# interface.net
KiCad netlist of a schematic drawn in EAGLE
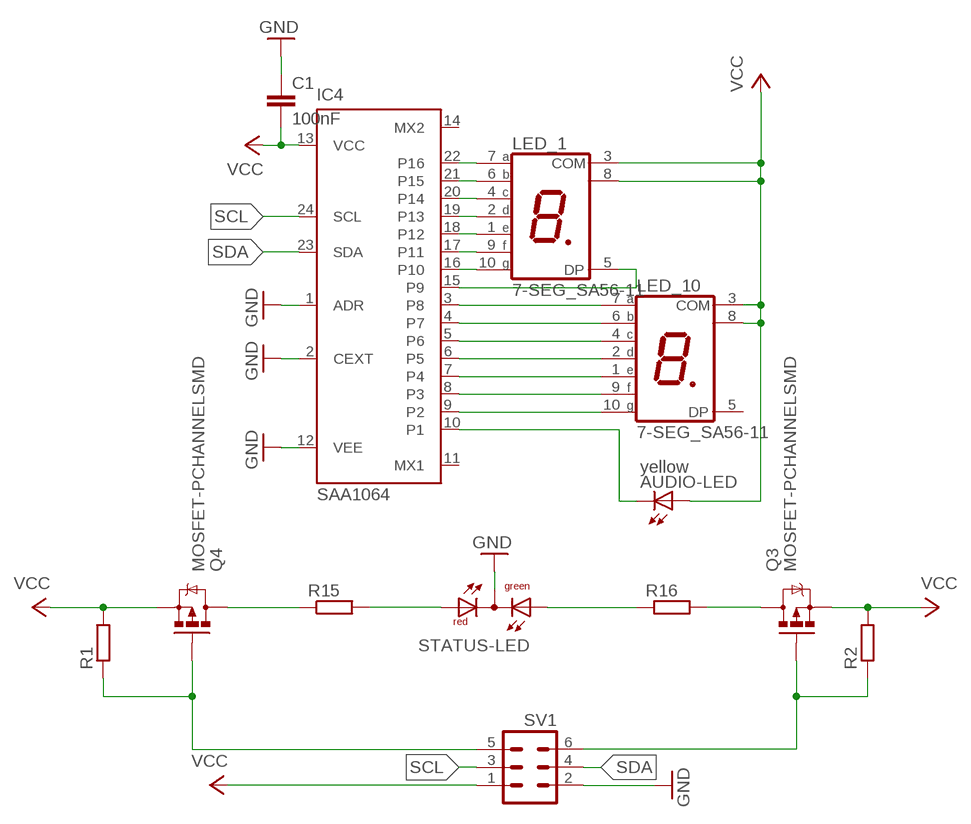
[diagram p0: schematic, sheet 1]
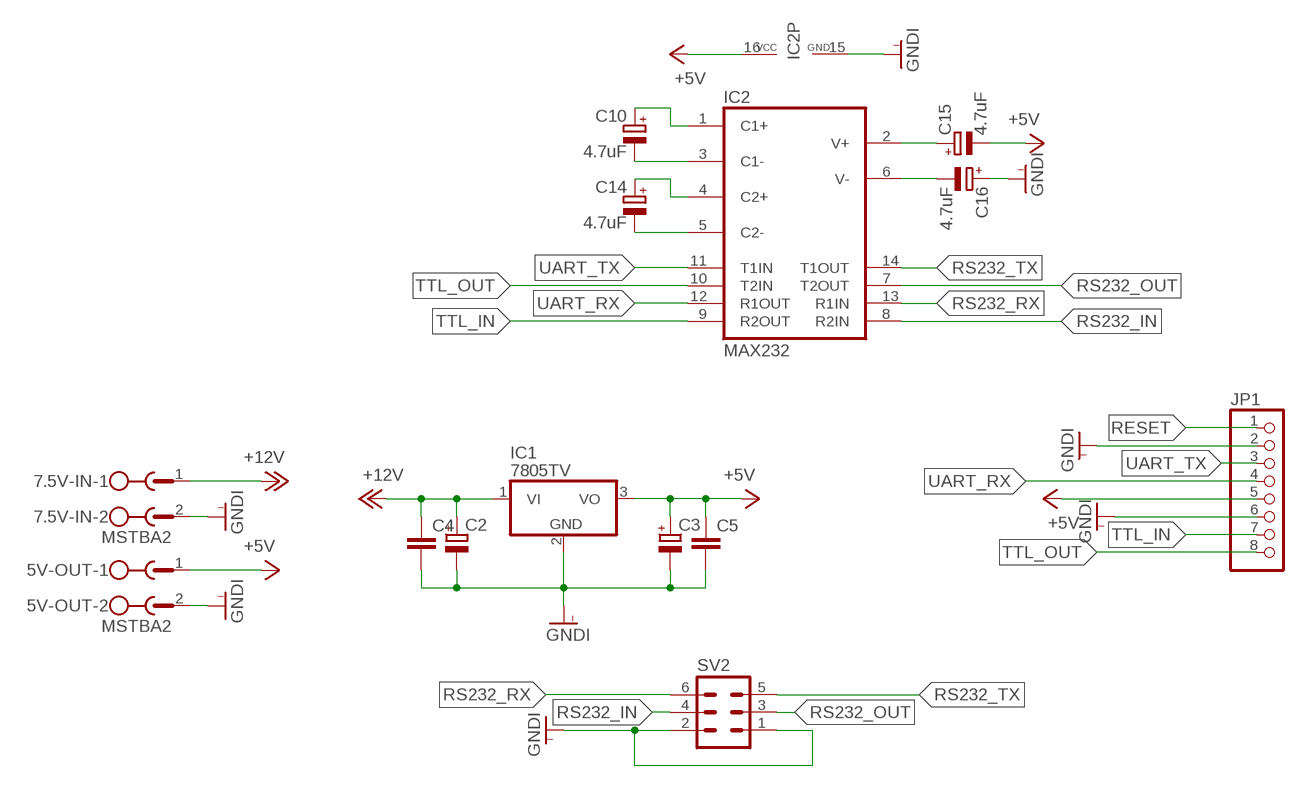
[diagram p1: schematic, sheet 2]
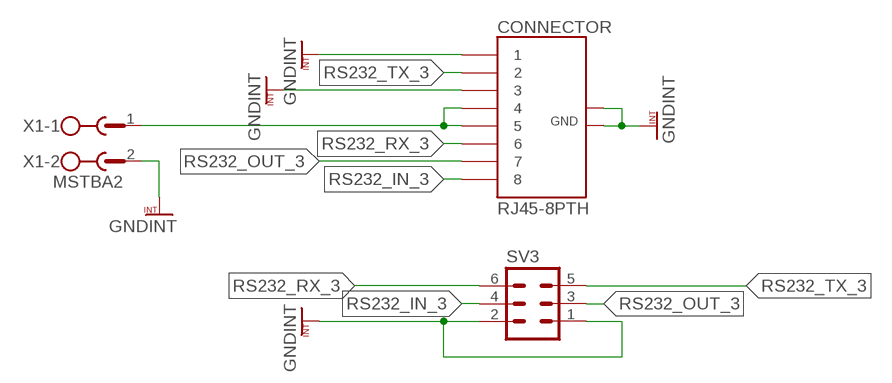
[diagram p2: schematic, sheet 3]

(export (version "E")
  (design (tool "Eeschema 10.0.6"))
  (components
    (comp (ref "CONNECTOR")
      (value "RJ45-8PTH")
      (footprint "eagle-import:RJ45-8")
      (libsource (lib "eagle-import") (part "RJ45-8PTH"))
    )
    (comp (ref "SV3")
      (value "ML6")
      (footprint "eagle-import:ML6")
      (libsource (lib "eagle-import") (part "ML6"))
    )
    (comp (ref "X1")
      (value "MSTBA2")
      (footprint "eagle-import:MSTBA2")
      (fields (field (name "MF") "FARNELL") (field (name "MPN") "1757242"))
      (libsource (lib "eagle-import") (part "MSTBA2"))
    )
    (comp (ref "AUDIO-LED")
      (value "yellow")
      (footprint "eagle-import:LED10MM")
      (libsource (lib "eagle-import") (part "LED10MM"))
    )
    (comp (ref "C1")
      (value "100nF")
      (footprint "eagle-import:C1206")
      (libsource (lib "eagle-import") (part "C-EUC1206"))
    )
    (comp (ref "IC4")
      (value "SAA1064")
      (footprint "eagle-import:DIL24-6")
      (fields (field (name "MPN") "SAA1064/N2,112"))
      (libsource (lib "eagle-import") (part "SAA1064"))
    )
    (comp (ref "LED_1")
      (value "7-SEG_SA56-11")
      (footprint "eagle-import:SA56-11")
      (libsource (lib "eagle-import") (part "7-SEG_SA56-11"))
    )
    (comp (ref "LED_10")
      (value "7-SEG_SA56-11")
      (footprint "eagle-import:SA56-11")
      (libsource (lib "eagle-import") (part "7-SEG_SA56-11"))
    )
    (comp (ref "Q3")
      (value "MOSFET-PCHANNELSMD")
      (footprint "eagle-import:SOT23-3")
      (libsource (lib "eagle-import") (part "MOSFET-PCHANNELSMD"))
    )
    (comp (ref "Q4")
      (value "MOSFET-PCHANNELSMD")
      (footprint "eagle-import:SOT23-3")
      (libsource (lib "eagle-import") (part "MOSFET-PCHANNELSMD"))
    )
    (comp (ref "R1")
      (value "R-EU_R1206")
      (footprint "eagle-import:R1206")
      (libsource (lib "eagle-import") (part "R-EU_R1206"))
    )
    (comp (ref "R2")
      (value "R-EU_R1206")
      (footprint "eagle-import:R1206")
      (libsource (lib "eagle-import") (part "R-EU_R1206"))
    )
    (comp (ref "R15")
      (value "R-EU_R1206")
      (footprint "eagle-import:R1206")
      (libsource (lib "eagle-import") (part "R-EU_R1206"))
    )
    (comp (ref "R16")
      (value "R-EU_R1206")
      (footprint "eagle-import:R1206")
      (libsource (lib "eagle-import") (part "R-EU_R1206"))
    )
    (comp (ref "STATUS-LED")
      (value "DUOLED-RG-C")
      (footprint "eagle-import:DUOLED-C-5MM")
      (libsource (lib "eagle-import") (part "DUOLED-RG-C"))
    )
    (comp (ref "SV1")
      (value "ML6SMD2")
      (footprint "eagle-import:ML6_SMD2")
      (libsource (lib "eagle-import") (part "ML6SMD2"))
    )
    (comp (ref "5V-OUT")
      (value "MSTBA2")
      (footprint "eagle-import:MSTBA2")
      (fields (field (name "MF") "FARNELL") (field (name "MPN") "1757242"))
      (libsource (lib "eagle-import") (part "MSTBA2"))
    )
    (comp (ref "7.5V-IN")
      (value "MSTBA2")
      (footprint "eagle-import:MSTBA2")
      (fields (field (name "MF") "FARNELL") (field (name "MPN") "1757242"))
      (libsource (lib "eagle-import") (part "MSTBA2"))
    )
    (comp (ref "C2")
      (value "CPOL-EUE5-10.5")
      (footprint "eagle-import:E5-10,5")
      (libsource (lib "eagle-import") (part "CPOL-EUE5-10.5"))
    )
    (comp (ref "C3")
      (value "CPOL-EUE5-10.5")
      (footprint "eagle-import:E5-10,5")
      (libsource (lib "eagle-import") (part "CPOL-EUE5-10.5"))
    )
    (comp (ref "C4")
      (value "C-EUC1206")
      (footprint "eagle-import:C1206")
      (libsource (lib "eagle-import") (part "C-EUC1206"))
    )
    (comp (ref "C5")
      (value "C-EUC1206")
      (footprint "eagle-import:C1206")
      (libsource (lib "eagle-import") (part "C-EUC1206"))
    )
    (comp (ref "C10")
      (value "4.7uF")
      (footprint "eagle-import:E2-5")
      (libsource (lib "eagle-import") (part "CPOL-EUE2-5"))
    )
    (comp (ref "C14")
      (value "4.7uF")
      (footprint "eagle-import:E2-5")
      (libsource (lib "eagle-import") (part "CPOL-EUE2-5"))
    )
    (comp (ref "C15")
      (value "4.7uF")
      (footprint "eagle-import:E2-5")
      (libsource (lib "eagle-import") (part "CPOL-EUE2-5"))
    )
    (comp (ref "C16")
      (value "4.7uF")
      (footprint "eagle-import:E2-5")
      (libsource (lib "eagle-import") (part "CPOL-EUE2-5"))
    )
    (comp (ref "IC1")
      (value "7805TV")
      (footprint "eagle-import:TO220V")
      (libsource (lib "eagle-import") (part "78TV05"))
    )
    (comp (ref "IC2")
      (value "MAX232")
      (footprint "eagle-import:DIL16")
      (fields (field (name "MF") "MAXIM") (field (name "MPN") "MAX232ACPE+"))
      (libsource (lib "eagle-import") (part "MAX232"))
    )
    (comp (ref "JP1")
      (value "PINHD-1X8/90")
      (footprint "eagle-import:1X08_90")
      (libsource (lib "eagle-import") (part "PINHD-1X8/90"))
    )
    (comp (ref "SV2")
      (value "ML6")
      (footprint "eagle-import:ML6")
      (libsource (lib "eagle-import") (part "ML6"))
    )
  )
  (nets
    (net (code "1") (name "+5V") (class "Default")
      (node (ref "5V-OUT") (pin "1") (pinfunction "1_1") (pintype "passive"))
      (node (ref "C15") (pin "-") (pinfunction "-_-") (pintype "passive"))
      (node (ref "C3") (pin "+") (pinfunction "+_+") (pintype "passive"))
      (node (ref "C5") (pin "1") (pinfunction "1_1") (pintype "passive"))
      (node (ref "IC1") (pin "3") (pinfunction "VO_3") (pintype "passive"))
      (node (ref "IC2") (pin "16") (pinfunction "VCC_16") (pintype "power_in"))
      (node (ref "JP1") (pin "5") (pinfunction "5_5") (pintype "passive"))
    )
    (net (code "2") (name "+12V") (class "Default")
      (node (ref "7.5V-IN") (pin "1") (pinfunction "1_1") (pintype "passive"))
      (node (ref "C2") (pin "+") (pinfunction "+_+") (pintype "passive"))
      (node (ref "C4") (pin "1") (pinfunction "1_1") (pintype "passive"))
      (node (ref "IC1") (pin "1") (pinfunction "VI_1") (pintype "input"))
    )
    (net (code "3") (name "GND") (class "Default")
      (node (ref "C1") (pin "1") (pinfunction "1_1") (pintype "passive"))
      (node (ref "IC4") (pin "1") (pinfunction "ADR_1") (pintype "input"))
      (node (ref "IC4") (pin "12") (pinfunction "VEE_12") (pintype "power_in"))
      (node (ref "IC4") (pin "2") (pinfunction "CEXT_2") (pintype "input"))
      (node (ref "STATUS-LED") (pin "C") (pinfunction "C_C") (pintype "passive"))
      (node (ref "SV1") (pin "2") (pinfunction "2_2") (pintype "passive"))
    )
    (net (code "4") (name "GNDI") (class "Default")
      (node (ref "5V-OUT") (pin "2") (pinfunction "1_2") (pintype "passive"))
      (node (ref "7.5V-IN") (pin "2") (pinfunction "1_2") (pintype "passive"))
      (node (ref "C16") (pin "+") (pinfunction "+_+") (pintype "passive"))
      (node (ref "C2") (pin "-") (pinfunction "-_-") (pintype "passive"))
      (node (ref "C3") (pin "-") (pinfunction "-_-") (pintype "passive"))
      (node (ref "C4") (pin "2") (pinfunction "2_2") (pintype "passive"))
      (node (ref "C5") (pin "2") (pinfunction "2_2") (pintype "passive"))
      (node (ref "IC1") (pin "2") (pinfunction "GND_2") (pintype "passive"))
      (node (ref "IC2") (pin "15") (pinfunction "GND_15") (pintype "power_in"))
      (node (ref "JP1") (pin "2") (pinfunction "2_2") (pintype "passive"))
      (node (ref "JP1") (pin "6") (pinfunction "6_6") (pintype "passive"))
      (node (ref "SV2") (pin "1") (pinfunction "1_1") (pintype "passive"))
      (node (ref "SV2") (pin "2") (pinfunction "2_2") (pintype "passive"))
    )
    (net (code "5") (name "GNDINT") (class "Default")
      (node (ref "CONNECTOR") (pin "1") (pinfunction "1_1") (pintype "bidirectional"))
      (node (ref "CONNECTOR") (pin "3") (pinfunction "3_3") (pintype "bidirectional"))
      (node (ref "CONNECTOR") (pin "GND_1") (pinfunction "GND_1_GND_1") (pintype "bidirectional"))
      (node (ref "CONNECTOR") (pin "GND_2") (pinfunction "GND_2_GND_2") (pintype "bidirectional"))
      (node (ref "SV3") (pin "1") (pinfunction "1_1") (pintype "passive"))
      (node (ref "SV3") (pin "2") (pinfunction "2_2") (pintype "passive"))
      (node (ref "X1") (pin "2") (pinfunction "1_2") (pintype "passive"))
    )
    (net (code "6") (name "Net-(AUDIO-LED-C)") (class "Default")
      (node (ref "AUDIO-LED") (pin "K") (pinfunction "C_K") (pintype "passive"))
      (node (ref "IC4") (pin "10") (pinfunction "P1_10") (pintype "output"))
    )
    (net (code "7") (name "Net-(CONNECTOR-Pad4)") (class "Default")
      (node (ref "CONNECTOR") (pin "4") (pinfunction "4_4") (pintype "bidirectional"))
      (node (ref "CONNECTOR") (pin "5") (pinfunction "5_5") (pintype "bidirectional"))
      (node (ref "X1") (pin "1") (pinfunction "1_1") (pintype "passive"))
    )
    (net (code "8") (name "Net-(IC2A-C1+)") (class "Default")
      (node (ref "C10") (pin "+") (pinfunction "+_+") (pintype "passive"))
      (node (ref "IC2") (pin "1") (pinfunction "C1+_1") (pintype "bidirectional"))
    )
    (net (code "9") (name "Net-(IC2A-C1-)") (class "Default")
      (node (ref "C10") (pin "-") (pinfunction "-_-") (pintype "passive"))
      (node (ref "IC2") (pin "3") (pinfunction "C1-_3") (pintype "bidirectional"))
    )
    (net (code "10") (name "Net-(IC2A-C2+)") (class "Default")
      (node (ref "C14") (pin "+") (pinfunction "+_+") (pintype "passive"))
      (node (ref "IC2") (pin "4") (pinfunction "C2+_4") (pintype "bidirectional"))
    )
    (net (code "11") (name "Net-(IC2A-C2-)") (class "Default")
      (node (ref "C14") (pin "-") (pinfunction "-_-") (pintype "passive"))
      (node (ref "IC2") (pin "5") (pinfunction "C2-_5") (pintype "bidirectional"))
    )
    (net (code "12") (name "Net-(IC2A-V+)") (class "Default")
      (node (ref "C15") (pin "+") (pinfunction "+_+") (pintype "passive"))
      (node (ref "IC2") (pin "2") (pinfunction "V+_2") (pintype "bidirectional"))
    )
    (net (code "13") (name "Net-(IC2A-V-)") (class "Default")
      (node (ref "C16") (pin "-") (pinfunction "-_-") (pintype "passive"))
      (node (ref "IC2") (pin "6") (pinfunction "V-_6") (pintype "bidirectional"))
    )
    (net (code "14") (name "Net-(IC4-P2)") (class "Default")
      (node (ref "IC4") (pin "9") (pinfunction "P2_9") (pintype "output"))
      (node (ref "LED_10") (pin "10") (pinfunction "G_10") (pintype "passive"))
    )
    (net (code "15") (name "Net-(IC4-P3)") (class "Default")
      (node (ref "IC4") (pin "8") (pinfunction "P3_8") (pintype "output"))
      (node (ref "LED_10") (pin "9") (pinfunction "F_9") (pintype "passive"))
    )
    (net (code "16") (name "Net-(IC4-P4)") (class "Default")
      (node (ref "IC4") (pin "7") (pinfunction "P4_7") (pintype "output"))
      (node (ref "LED_10") (pin "1") (pinfunction "E_1") (pintype "passive"))
    )
    (net (code "17") (name "Net-(IC4-P5)") (class "Default")
      (node (ref "IC4") (pin "6") (pinfunction "P5_6") (pintype "output"))
      (node (ref "LED_10") (pin "2") (pinfunction "D_2") (pintype "passive"))
    )
    (net (code "18") (name "Net-(IC4-P6)") (class "Default")
      (node (ref "IC4") (pin "5") (pinfunction "P6_5") (pintype "output"))
      (node (ref "LED_10") (pin "4") (pinfunction "C_4") (pintype "passive"))
    )
    (net (code "19") (name "Net-(IC4-P7)") (class "Default")
      (node (ref "IC4") (pin "4") (pinfunction "P7_4") (pintype "output"))
      (node (ref "LED_10") (pin "6") (pinfunction "B_6") (pintype "passive"))
    )
    (net (code "20") (name "Net-(IC4-P8)") (class "Default")
      (node (ref "IC4") (pin "3") (pinfunction "P8_3") (pintype "output"))
      (node (ref "LED_10") (pin "7") (pinfunction "A_7") (pintype "passive"))
    )
    (net (code "21") (name "Net-(IC4-P9)") (class "Default")
      (node (ref "IC4") (pin "15") (pinfunction "P9_15") (pintype "output"))
      (node (ref "LED_1") (pin "5") (pinfunction "DP_5") (pintype "passive"))
    )
    (net (code "22") (name "Net-(IC4-P10)") (class "Default")
      (node (ref "IC4") (pin "16") (pinfunction "P10_16") (pintype "output"))
      (node (ref "LED_1") (pin "10") (pinfunction "G_10") (pintype "passive"))
    )
    (net (code "23") (name "Net-(IC4-P11)") (class "Default")
      (node (ref "IC4") (pin "17") (pinfunction "P11_17") (pintype "output"))
      (node (ref "LED_1") (pin "9") (pinfunction "F_9") (pintype "passive"))
    )
    (net (code "24") (name "Net-(IC4-P12)") (class "Default")
      (node (ref "IC4") (pin "18") (pinfunction "P12_18") (pintype "output"))
      (node (ref "LED_1") (pin "1") (pinfunction "E_1") (pintype "passive"))
    )
    (net (code "25") (name "Net-(IC4-P13)") (class "Default")
      (node (ref "IC4") (pin "19") (pinfunction "P13_19") (pintype "output"))
      (node (ref "LED_1") (pin "2") (pinfunction "D_2") (pintype "passive"))
    )
    (net (code "26") (name "Net-(IC4-P14)") (class "Default")
      (node (ref "IC4") (pin "20") (pinfunction "P14_20") (pintype "output"))
      (node (ref "LED_1") (pin "4") (pinfunction "C_4") (pintype "passive"))
    )
    (net (code "27") (name "Net-(IC4-P15)") (class "Default")
      (node (ref "IC4") (pin "21") (pinfunction "P15_21") (pintype "output"))
      (node (ref "LED_1") (pin "6") (pinfunction "B_6") (pintype "passive"))
    )
    (net (code "28") (name "Net-(IC4-P16)") (class "Default")
      (node (ref "IC4") (pin "22") (pinfunction "P16_22") (pintype "output"))
      (node (ref "LED_1") (pin "7") (pinfunction "A_7") (pintype "passive"))
    )
    (net (code "29") (name "Net-(Q3-D)") (class "Default")
      (node (ref "Q3") (pin "3") (pinfunction "D_3") (pintype "passive"))
      (node (ref "R16") (pin "2") (pinfunction "2_2") (pintype "passive"))
    )
    (net (code "30") (name "Net-(Q3-G)") (class "Default")
      (node (ref "Q3") (pin "1") (pinfunction "G_1") (pintype "passive"))
      (node (ref "R2") (pin "1") (pinfunction "1_1") (pintype "passive"))
      (node (ref "SV1") (pin "6") (pinfunction "6_6") (pintype "passive"))
    )
    (net (code "31") (name "Net-(Q4-D)") (class "Default")
      (node (ref "Q4") (pin "3") (pinfunction "D_3") (pintype "passive"))
      (node (ref "R15") (pin "1") (pinfunction "1_1") (pintype "passive"))
    )
    (net (code "32") (name "Net-(Q4-G)") (class "Default")
      (node (ref "Q4") (pin "1") (pinfunction "G_1") (pintype "passive"))
      (node (ref "R1") (pin "1") (pinfunction "1_1") (pintype "passive"))
      (node (ref "SV1") (pin "5") (pinfunction "5_5") (pintype "passive"))
    )
    (net (code "33") (name "Net-(R15-Pad2)") (class "Default")
      (node (ref "R15") (pin "2") (pinfunction "2_2") (pintype "passive"))
      (node (ref "STATUS-LED") (pin "AR") (pinfunction "AR_AR") (pintype "passive"))
    )
    (net (code "34") (name "Net-(STATUS-LED-AG)") (class "Default")
      (node (ref "R16") (pin "1") (pinfunction "1_1") (pintype "passive"))
      (node (ref "STATUS-LED") (pin "AX") (pinfunction "AG_AX") (pintype "passive"))
    )
    (net (code "35") (name "RESET") (class "Default")
      (node (ref "JP1") (pin "1") (pinfunction "1_1") (pintype "passive"))
    )
    (net (code "36") (name "RS232_IN") (class "Default")
      (node (ref "IC2") (pin "8") (pinfunction "R2IN_8") (pintype "input"))
      (node (ref "SV2") (pin "4") (pinfunction "4_4") (pintype "passive"))
    )
    (net (code "37") (name "RS232_IN_3") (class "Default")
      (node (ref "CONNECTOR") (pin "8") (pinfunction "8_8") (pintype "bidirectional"))
      (node (ref "SV3") (pin "4") (pinfunction "4_4") (pintype "passive"))
    )
    (net (code "38") (name "RS232_OUT") (class "Default")
      (node (ref "IC2") (pin "7") (pinfunction "T2OUT_7") (pintype "output"))
      (node (ref "SV2") (pin "3") (pinfunction "3_3") (pintype "passive"))
    )
    (net (code "39") (name "RS232_OUT_3") (class "Default")
      (node (ref "CONNECTOR") (pin "7") (pinfunction "7_7") (pintype "bidirectional"))
      (node (ref "SV3") (pin "3") (pinfunction "3_3") (pintype "passive"))
    )
    (net (code "40") (name "RS232_RX") (class "Default")
      (node (ref "IC2") (pin "13") (pinfunction "R1IN_13") (pintype "input"))
      (node (ref "SV2") (pin "6") (pinfunction "6_6") (pintype "passive"))
    )
    (net (code "41") (name "RS232_RX_3") (class "Default")
      (node (ref "CONNECTOR") (pin "6") (pinfunction "6_6") (pintype "bidirectional"))
      (node (ref "SV3") (pin "6") (pinfunction "6_6") (pintype "passive"))
    )
    (net (code "42") (name "RS232_TX") (class "Default")
      (node (ref "IC2") (pin "14") (pinfunction "T1OUT_14") (pintype "output"))
      (node (ref "SV2") (pin "5") (pinfunction "5_5") (pintype "passive"))
    )
    (net (code "43") (name "RS232_TX_3") (class "Default")
      (node (ref "CONNECTOR") (pin "2") (pinfunction "2_2") (pintype "bidirectional"))
      (node (ref "SV3") (pin "5") (pinfunction "5_5") (pintype "passive"))
    )
    (net (code "44") (name "SCL") (class "Default")
      (node (ref "IC4") (pin "24") (pinfunction "SCL_24") (pintype "input"))
      (node (ref "SV1") (pin "3") (pinfunction "3_3") (pintype "passive"))
    )
    (net (code "45") (name "SDA") (class "Default")
      (node (ref "IC4") (pin "23") (pinfunction "SDA_23") (pintype "input"))
      (node (ref "SV1") (pin "4") (pinfunction "4_4") (pintype "passive"))
    )
    (net (code "46") (name "TTL_IN") (class "Default")
      (node (ref "IC2") (pin "9") (pinfunction "R2OUT_9") (pintype "output"))
      (node (ref "JP1") (pin "7") (pinfunction "7_7") (pintype "passive"))
    )
    (net (code "47") (name "TTL_OUT") (class "Default")
      (node (ref "IC2") (pin "10") (pinfunction "T2IN_10") (pintype "input"))
      (node (ref "JP1") (pin "8") (pinfunction "8_8") (pintype "passive"))
    )
    (net (code "48") (name "UART_RX") (class "Default")
      (node (ref "IC2") (pin "12") (pinfunction "R1OUT_12") (pintype "output"))
      (node (ref "JP1") (pin "4") (pinfunction "4_4") (pintype "passive"))
    )
    (net (code "49") (name "UART_TX") (class "Default")
      (node (ref "IC2") (pin "11") (pinfunction "T1IN_11") (pintype "input"))
      (node (ref "JP1") (pin "3") (pinfunction "3_3") (pintype "passive"))
    )
    (net (code "50") (name "VCC") (class "Default")
      (node (ref "AUDIO-LED") (pin "A") (pinfunction "A_A") (pintype "passive"))
      (node (ref "C1") (pin "2") (pinfunction "2_2") (pintype "passive"))
      (node (ref "IC4") (pin "13") (pinfunction "VCC_13") (pintype "power_in"))
      (node (ref "LED_1") (pin "3") (pinfunction "COM_3") (pintype "passive"))
      (node (ref "LED_1") (pin "8") (pinfunction "COM_8") (pintype "passive"))
      (node (ref "LED_10") (pin "3") (pinfunction "COM_3") (pintype "passive"))
      (node (ref "LED_10") (pin "8") (pinfunction "COM_8") (pintype "passive"))
      (node (ref "Q3") (pin "2") (pinfunction "S_2") (pintype "passive"))
      (node (ref "Q4") (pin "2") (pinfunction "S_2") (pintype "passive"))
      (node (ref "R1") (pin "2") (pinfunction "2_2") (pintype "passive"))
      (node (ref "R2") (pin "2") (pinfunction "2_2") (pintype "passive"))
      (node (ref "SV1") (pin "1") (pinfunction "1_1") (pintype "passive"))
    )
    (net (code "51") (name "unconnected-(IC4-MX1-Pad11)") (class "Default")
      (node (ref "IC4") (pin "11") (pinfunction "MX1_11") (pintype "output"))
    )
    (net (code "52") (name "unconnected-(IC4-MX2-Pad14)") (class "Default")
      (node (ref "IC4") (pin "14") (pinfunction "MX2_14") (pintype "output"))
    )
    (net (code "53") (name "unconnected-(LED_10-DP-Pad5)") (class "Default")
      (node (ref "LED_10") (pin "5") (pinfunction "DP_5") (pintype "passive"))
    )
  )
)
